# SheetMCU.net
KiCad netlist of a schematic drawn in Altium Designer
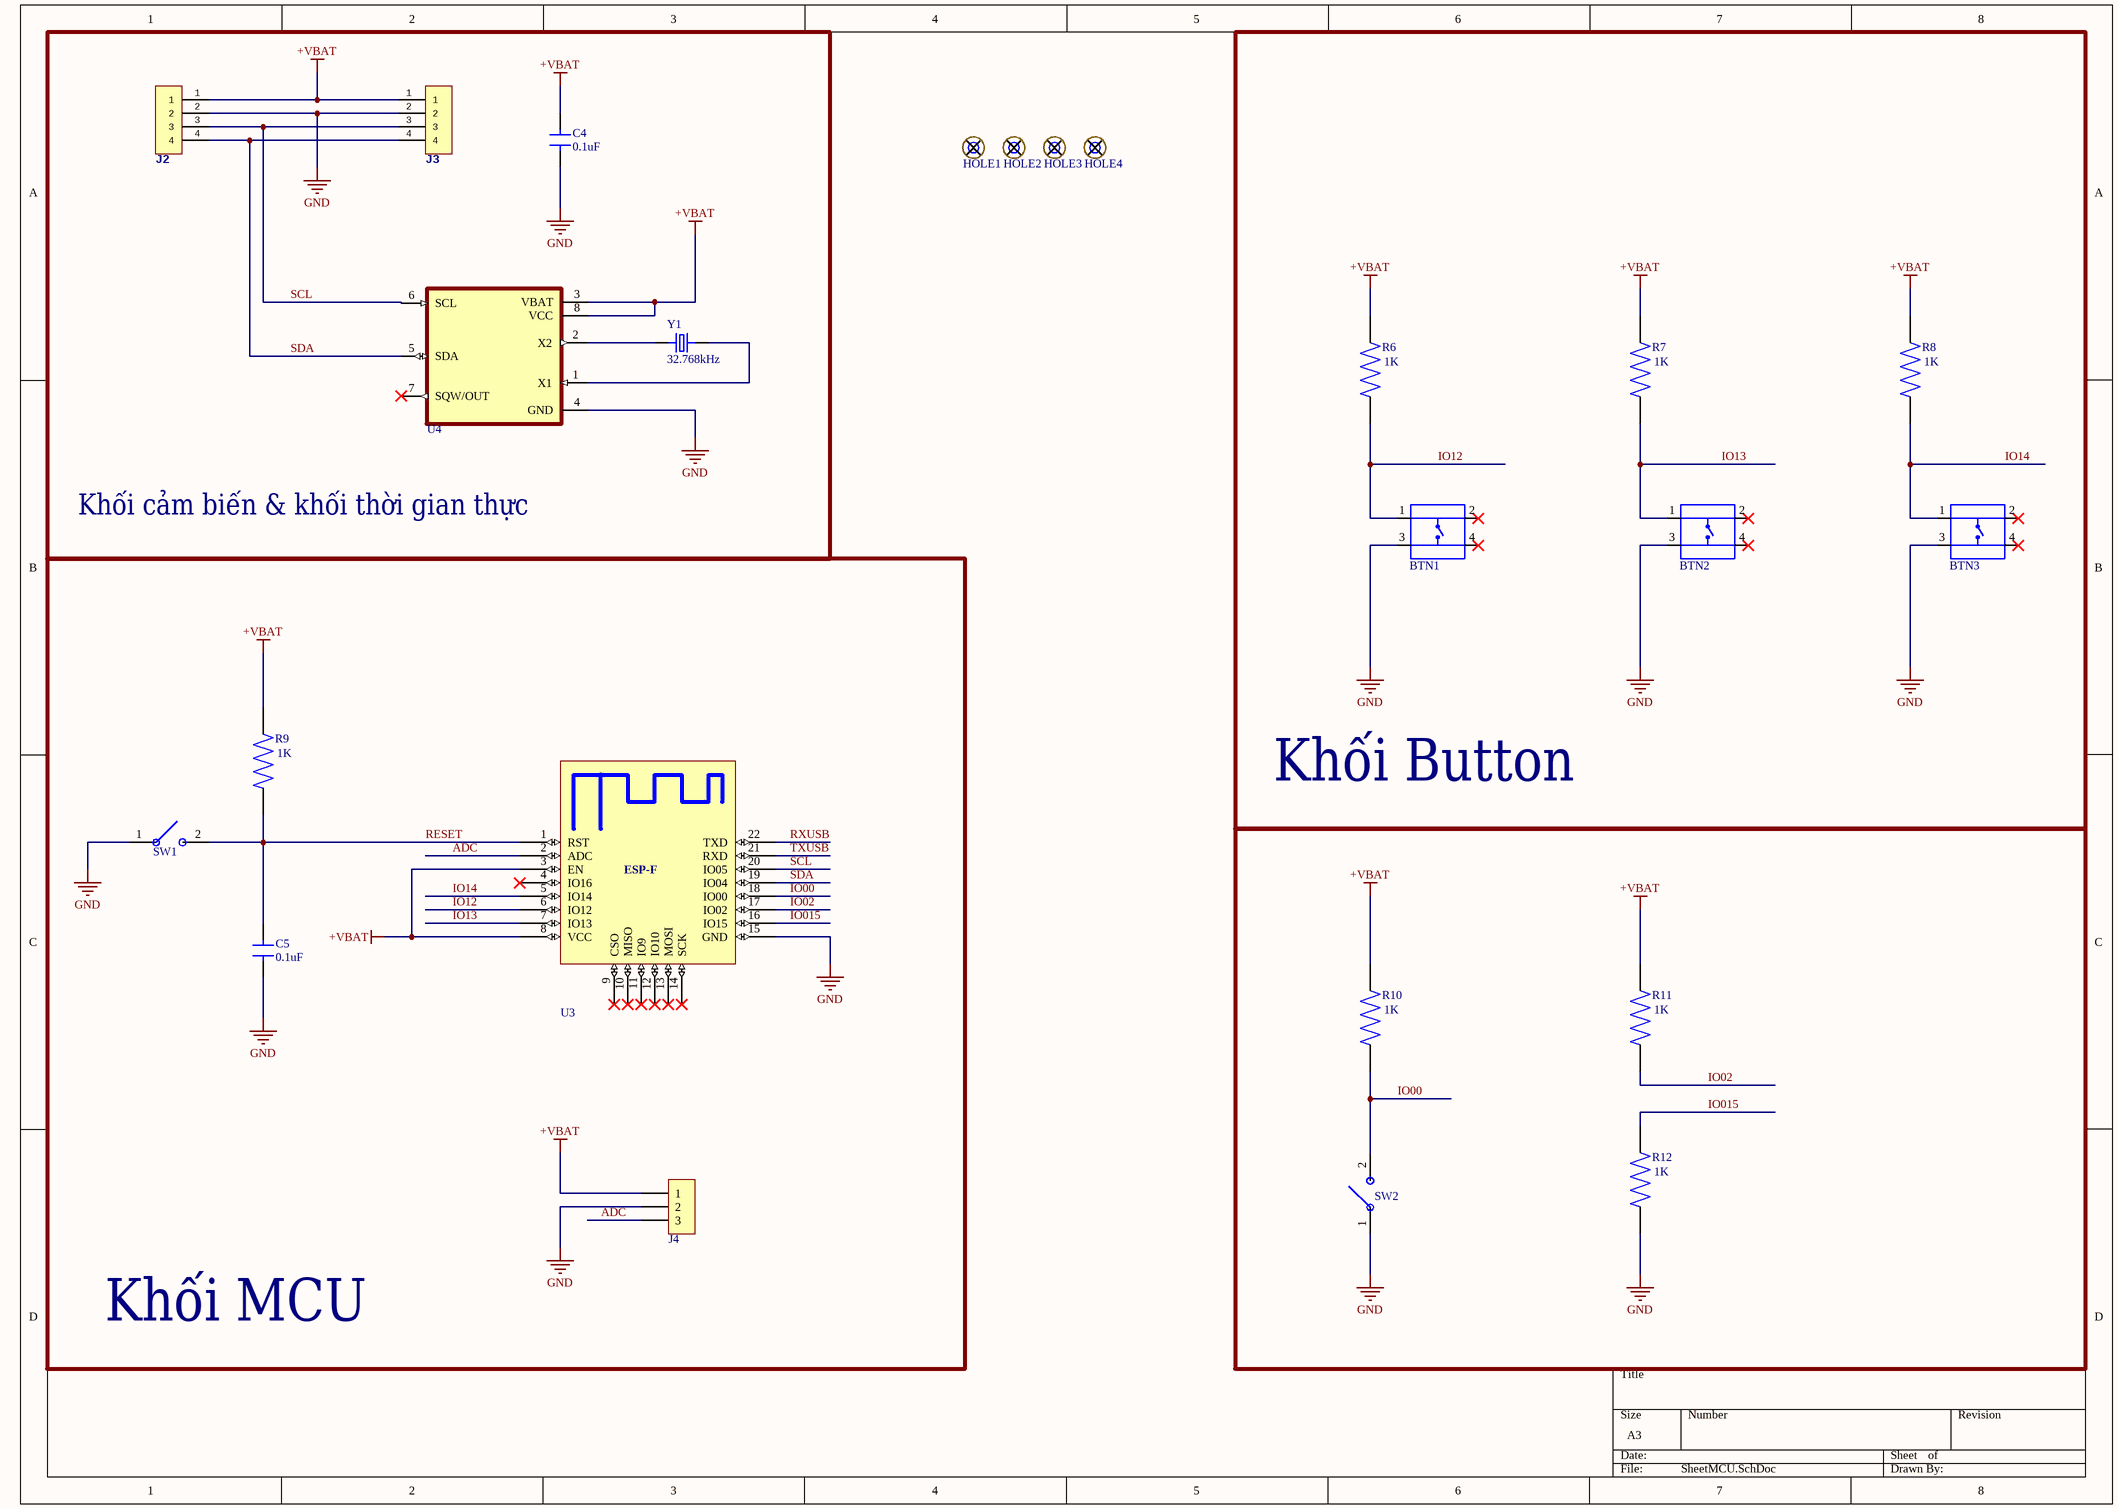
[diagram p0: SheetMCU.SchDoc]

(export (version "E")
  (design (tool "Eeschema 10.0.6"))
  (components
    (comp (ref "BTN1")
      (value "button 4x4")
      (footprint "SW_2-1825910-7")
      (description "Switch Tactile N.O. SPST Round Button PC Pins 0.05A 50VDC 1.57N Thru-Hole")
      (fields
        (field (name "MANUFACTURER") "E-Switch")
        (field (name "MANUFACTURER PART NUMBER") "TL1105BF160Q")
      )
      (libsource (lib "SchlibWatch") (part "TL1105BF160Q"))
    )
    (comp (ref "BTN2")
      (value "button 4x4")
      (footprint "SW_2-1825910-7")
      (description "Switch Tactile N.O. SPST Round Button PC Pins 0.05A 50VDC 1.57N Thru-Hole")
      (fields
        (field (name "MANUFACTURER") "E-Switch")
        (field (name "MANUFACTURER PART NUMBER") "TL1105BF160Q")
      )
      (libsource (lib "SchlibWatch") (part "TL1105BF160Q"))
    )
    (comp (ref "BTN3")
      (value "button 4x4")
      (footprint "SW_2-1825910-7")
      (description "Switch Tactile N.O. SPST Round Button PC Pins 0.05A 50VDC 1.57N Thru-Hole")
      (fields
        (field (name "MANUFACTURER") "E-Switch")
        (field (name "MANUFACTURER PART NUMBER") "TL1105BF160Q")
      )
      (libsource (lib "SchlibWatch") (part "TL1105BF160Q"))
    )
    (comp (ref "C4")
      (value "0.1uF")
      (footprint "CAP104 0.1UF 50V")
      (description "Cap Ceramic 0.1uF 50V X7R 10% SMD 2.0 x 1.2 mm 125 C Paper T/R")
      (fields
        (field (name "MANUFACTURER") "KEMET")
        (field (name "MANUFACTURER PART NUMBER") "C0805C104K5RACTU")
      )
      (libsource (lib "SchlibWatch") (part "C0805C104K5RACTU"))
    )
    (comp (ref "C5")
      (value "0.1uF")
      (footprint "CAP104 0.1UF 50V")
      (description "Cap Ceramic 0.1uF 50V X7R 10% SMD 2.0 x 1.2 mm 125 C Paper T/R")
      (fields
        (field (name "MANUFACTURER") "KEMET")
        (field (name "MANUFACTURER PART NUMBER") "C0805C104K5RACTU")
      )
      (libsource (lib "SchlibWatch") (part "C0805C104K5RACTU"))
    )
    (comp (ref "HOLE1")
      (value "Hole")
      (footprint "Hole 2MM")
      (description "Hole 3mm")
      (libsource (lib "SchlibWatch") (part "Hole 2mm"))
    )
    (comp (ref "HOLE2")
      (value "Hole")
      (footprint "Hole 2MM")
      (description "Hole 3mm")
      (libsource (lib "SchlibWatch") (part "Hole 2mm"))
    )
    (comp (ref "HOLE3")
      (value "Hole")
      (footprint "Hole 2MM")
      (description "Hole 3mm")
      (libsource (lib "SchlibWatch") (part "Hole 2mm"))
    )
    (comp (ref "HOLE4")
      (value "Hole")
      (footprint "Hole 2MM")
      (description "Hole 3mm")
      (libsource (lib "SchlibWatch") (part "Hole 2mm"))
    )
    (comp (ref "J2")
      (value "SAMTEC-HTSW-104-07-X-SJ")
      (footprint "Conn 4 Pos")
      (description "CONN HEADER 4 POS 2.54mm")
      (libsource (lib "SchlibWatch") (part "SAMTEC-HTSW-104-07-X-SJ"))
    )
    (comp (ref "J3")
      (value "SAMTEC-HTSW-104-07-X-SJ")
      (footprint "Conn 4 Pos")
      (description "CONN HEADER 4 POS 2.54mm")
      (libsource (lib "") (part "SAMTEC-HTSW-104-07-X-SJ_1"))
    )
    (comp (ref "J4")
      (value "CONN HEADER VERT 3POS 2.54MM")
      (footprint "CONN HEADER VERT 3POS 2.54MM")
      (description "Conn Unshrouded Header HDR 3 POS 2.54mm Solder ST Thru-Hole")
      (fields
        (field (name "MANUFACTURER") "TE Connectivity")
        (field (name "MANUFACTURER PART NUMBER") "87220-3")
      )
      (libsource (lib "SchlibWatch") (part "87220-3"))
    )
    (comp (ref "R6")
      (value "1K")
      (footprint "RC0805 1K OHM")
      (description "贴片电阻 1000Ω ± 1.00% 0.125W ± 100ppm/℃ 0805")
      (fields
        (field (name "MANUFACTURER") "Yageo")
        (field (name "MANUFACTURER PART NUMBER") "RC0805FR-071KL")
      )
      (libsource (lib "SchlibWatch") (part "RC0805FR-071KL"))
    )
    (comp (ref "R7")
      (value "1K")
      (footprint "RC0805 1K OHM")
      (description "贴片电阻 1000Ω ± 1.00% 0.125W ± 100ppm/℃ 0805")
      (fields
        (field (name "MANUFACTURER") "Yageo")
        (field (name "MANUFACTURER PART NUMBER") "RC0805FR-071KL")
      )
      (libsource (lib "SchlibWatch") (part "RC0805FR-071KL"))
    )
    (comp (ref "R8")
      (value "1K")
      (footprint "RC0805 1K OHM")
      (description "贴片电阻 1000Ω ± 1.00% 0.125W ± 100ppm/℃ 0805")
      (fields
        (field (name "MANUFACTURER") "Yageo")
        (field (name "MANUFACTURER PART NUMBER") "RC0805FR-071KL")
      )
      (libsource (lib "SchlibWatch") (part "RC0805FR-071KL"))
    )
    (comp (ref "R9")
      (value "1K")
      (footprint "RC0805 1K OHM")
      (description "贴片电阻 1000Ω ± 1.00% 0.125W ± 100ppm/℃ 0805")
      (fields
        (field (name "MANUFACTURER") "Yageo")
        (field (name "MANUFACTURER PART NUMBER") "RC0805FR-071KL")
      )
      (libsource (lib "SchlibWatch") (part "RC0805FR-071KL"))
    )
    (comp (ref "R10")
      (value "1K")
      (footprint "RC0805 1K OHM")
      (description "贴片电阻 1000Ω ± 1.00% 0.125W ± 100ppm/℃ 0805")
      (fields
        (field (name "MANUFACTURER") "Yageo")
        (field (name "MANUFACTURER PART NUMBER") "RC0805FR-071KL")
      )
      (libsource (lib "SchlibWatch") (part "RC0805FR-071KL"))
    )
    (comp (ref "R11")
      (value "1K")
      (footprint "RC0805 1K OHM")
      (description "贴片电阻 1000Ω ± 1.00% 0.125W ± 100ppm/℃ 0805")
      (fields
        (field (name "MANUFACTURER") "Yageo")
        (field (name "MANUFACTURER PART NUMBER") "RC0805FR-071KL")
      )
      (libsource (lib "SchlibWatch") (part "RC0805FR-071KL"))
    )
    (comp (ref "R12")
      (value "1K")
      (footprint "RC0805 1K OHM")
      (description "贴片电阻 1000Ω ± 1.00% 0.125W ± 100ppm/℃ 0805")
      (fields
        (field (name "MANUFACTURER") "Yageo")
        (field (name "MANUFACTURER PART NUMBER") "RC0805FR-071KL")
      )
      (libsource (lib "SchlibWatch") (part "RC0805FR-071KL"))
    )
    (comp (ref "SW1")
      (value "Switch")
      (footprint "PTS636 SM43J SMTR LFS")
      (description "Switch Reset")
      (fields
        (field (name "MANUFACTURER") "ITT C&K")
        (field (name "MANUFACTURER PART NUMBER") "PTS636SM43JSMTRLFS")
      )
      (libsource (lib "SchlibWatch") (part "PTS636SM43JSMTRLFS"))
    )
    (comp (ref "SW2")
      (value "Switch")
      (footprint "PTS636 SM43J SMTR LFS")
      (description "Switch Reset")
      (fields
        (field (name "MANUFACTURER") "ITT C&K")
        (field (name "MANUFACTURER PART NUMBER") "PTS636SM43JSMTRLFS")
      )
      (libsource (lib "SchlibWatch") (part "PTS636SM43JSMTRLFS"))
    )
    (comp (ref "U3")
      (value "ESP8266 ESP_F")
      (footprint "ESP8266 ESP-F")
      (description "ESP8266 SMT MODULE")
      (fields
        (field (name "MANUFACTURER") "Adafruit Industries")
        (field (name "MANUFACTURER PART NUMBER") "2491")
      )
      (libsource (lib "SchlibWatch") (part "2491"))
    )
    (comp (ref "U4")
      (value "DS1307Z+")
      (footprint "SOIC127P600X175-8N")
      (description "Real Time Clock _RTC_ IC Clock/Calendar 56B IÂ²C, 2-Wire Serial 8-SOIC _0.154, 3.90mm Width_")
      (fields (field (name "MF") "Maxim Integrated") (field (name "MP") "DS1307Z"))
      (libsource (lib "SchlibWatch") (part "DS1307Z+"))
    )
    (comp (ref "Y1")
      (value "32.768kHz")
      (footprint "XTAL_ECS-3X8X")
      (description "32.768kHz Â±20ppm Crystal 12.5pF 35 kOhms Cylindrical Can, Radial")
      (fields (field (name "MF") "ECS Inc.") (field (name "MP") "ECS-3X8X"))
      (libsource (lib "SchlibWatch") (part "ECS-3X8X"))
    )
  )
  (nets
    (net (code "1") (name "+VBAT") (class "Default")
      (node (ref "C4") (pin "2") (pinfunction "2_2") (pintype "passive"))
      (node (ref "J2") (pin "1") (pinfunction "1_1") (pintype "passive"))
      (node (ref "J3") (pin "1") (pinfunction "1_1") (pintype "passive"))
      (node (ref "J4") (pin "1") (pinfunction "1_1") (pintype "passive"))
      (node (ref "R10") (pin "2") (pinfunction "2_2") (pintype "passive"))
      (node (ref "R11") (pin "2") (pinfunction "2_2") (pintype "passive"))
      (node (ref "R6") (pin "2") (pinfunction "2_2") (pintype "passive"))
      (node (ref "R7") (pin "2") (pinfunction "2_2") (pintype "passive"))
      (node (ref "R8") (pin "2") (pinfunction "2_2") (pintype "passive"))
      (node (ref "R9") (pin "2") (pinfunction "2_2") (pintype "passive"))
      (node (ref "U3") (pin "3") (pinfunction "EN_3") (pintype "bidirectional"))
      (node (ref "U3") (pin "8") (pinfunction "VCC_8") (pintype "bidirectional"))
      (node (ref "U4") (pin "3") (pinfunction "VBAT_3") (pintype "power_in"))
      (node (ref "U4") (pin "8") (pinfunction "VCC_8") (pintype "power_in"))
    )
    (net (code "2") (name "/ADC") (class "Default")
      (node (ref "J4") (pin "3") (pinfunction "3_3") (pintype "passive"))
      (node (ref "U3") (pin "2") (pinfunction "ADC_2") (pintype "bidirectional"))
    )
    (net (code "3") (name "/IO00") (class "Default")
      (node (ref "R10") (pin "1") (pinfunction "1_1") (pintype "passive"))
      (node (ref "SW2") (pin "2") (pinfunction "2_2") (pintype "passive"))
      (node (ref "U3") (pin "18") (pinfunction "IO00_18") (pintype "bidirectional"))
    )
    (net (code "4") (name "/IO02") (class "Default")
      (node (ref "R11") (pin "1") (pinfunction "1_1") (pintype "passive"))
      (node (ref "U3") (pin "17") (pinfunction "IO02_17") (pintype "bidirectional"))
    )
    (net (code "5") (name "/IO12") (class "Default")
      (node (ref "BTN1") (pin "1") (pinfunction "1_1") (pintype "passive"))
      (node (ref "R6") (pin "1") (pinfunction "1_1") (pintype "passive"))
      (node (ref "U3") (pin "6") (pinfunction "IO12_6") (pintype "bidirectional"))
    )
    (net (code "6") (name "/IO13") (class "Default")
      (node (ref "BTN2") (pin "1") (pinfunction "1_1") (pintype "passive"))
      (node (ref "R7") (pin "1") (pinfunction "1_1") (pintype "passive"))
      (node (ref "U3") (pin "7") (pinfunction "IO13_7") (pintype "bidirectional"))
    )
    (net (code "7") (name "/IO14") (class "Default")
      (node (ref "BTN3") (pin "1") (pinfunction "1_1") (pintype "passive"))
      (node (ref "R8") (pin "1") (pinfunction "1_1") (pintype "passive"))
      (node (ref "U3") (pin "5") (pinfunction "IO14_5") (pintype "bidirectional"))
    )
    (net (code "8") (name "/IO015") (class "Default")
      (node (ref "R12") (pin "2") (pinfunction "2_2") (pintype "passive"))
      (node (ref "U3") (pin "16") (pinfunction "IO15_16") (pintype "bidirectional"))
    )
    (net (code "9") (name "/RESET") (class "Default")
      (node (ref "C5") (pin "2") (pinfunction "2_2") (pintype "passive"))
      (node (ref "R9") (pin "1") (pinfunction "1_1") (pintype "passive"))
      (node (ref "SW1") (pin "2") (pinfunction "2_2") (pintype "passive"))
      (node (ref "U3") (pin "1") (pinfunction "RST_1") (pintype "bidirectional"))
    )
    (net (code "10") (name "/RXUSB") (class "Default")
      (node (ref "U3") (pin "22") (pinfunction "TXD_22") (pintype "bidirectional"))
    )
    (net (code "11") (name "/SCL") (class "Default")
      (node (ref "J2") (pin "3") (pinfunction "3_3") (pintype "passive"))
      (node (ref "J3") (pin "3") (pinfunction "3_3") (pintype "passive"))
      (node (ref "U3") (pin "20") (pinfunction "IO05_20") (pintype "bidirectional"))
      (node (ref "U4") (pin "6") (pinfunction "SCL_6") (pintype "input"))
    )
    (net (code "12") (name "/SDA") (class "Default")
      (node (ref "J2") (pin "4") (pinfunction "4_4") (pintype "passive"))
      (node (ref "J3") (pin "4") (pinfunction "4_4") (pintype "passive"))
      (node (ref "U3") (pin "19") (pinfunction "IO04_19") (pintype "bidirectional"))
      (node (ref "U4") (pin "5") (pinfunction "SDA_5") (pintype "bidirectional"))
    )
    (net (code "13") (name "/TXUSB") (class "Default")
      (node (ref "U3") (pin "21") (pinfunction "RXD_21") (pintype "bidirectional"))
    )
    (net (code "14") (name "GND") (class "Default")
      (node (ref "BTN1") (pin "3") (pinfunction "3_3") (pintype "passive"))
      (node (ref "BTN2") (pin "3") (pinfunction "3_3") (pintype "passive"))
      (node (ref "BTN3") (pin "3") (pinfunction "3_3") (pintype "passive"))
      (node (ref "C4") (pin "1") (pinfunction "1_1") (pintype "passive"))
      (node (ref "C5") (pin "1") (pinfunction "1_1") (pintype "passive"))
      (node (ref "J2") (pin "2") (pinfunction "2_2") (pintype "passive"))
      (node (ref "J3") (pin "2") (pinfunction "2_2") (pintype "passive"))
      (node (ref "J4") (pin "2") (pinfunction "2_2") (pintype "passive"))
      (node (ref "R12") (pin "1") (pinfunction "1_1") (pintype "passive"))
      (node (ref "SW1") (pin "1") (pinfunction "1_1") (pintype "passive"))
      (node (ref "SW2") (pin "1") (pinfunction "1_1") (pintype "passive"))
      (node (ref "U3") (pin "15") (pinfunction "GND_15") (pintype "bidirectional"))
      (node (ref "U4") (pin "4") (pinfunction "GND_4") (pintype "power_in"))
    )
    (net (code "15") (name "Net-(U4-X1)") (class "Default")
      (node (ref "U4") (pin "1") (pinfunction "X1_1") (pintype "input"))
      (node (ref "Y1") (pin "2") (pinfunction "2_2") (pintype "passive"))
    )
    (net (code "16") (name "Net-(U4-X2)") (class "Default")
      (node (ref "U4") (pin "2") (pinfunction "X2_2") (pintype "output"))
      (node (ref "Y1") (pin "1") (pinfunction "1_1") (pintype "passive"))
    )
    (net (code "17") (name "unconnected-(BTN1-Pad2)") (class "Default")
      (node (ref "BTN1") (pin "2") (pinfunction "2_2") (pintype "passive+no_connect"))
    )
    (net (code "18") (name "unconnected-(BTN1-Pad4)") (class "Default")
      (node (ref "BTN1") (pin "4") (pinfunction "4_4") (pintype "passive+no_connect"))
    )
    (net (code "19") (name "unconnected-(BTN2-Pad2)") (class "Default")
      (node (ref "BTN2") (pin "2") (pinfunction "2_2") (pintype "passive+no_connect"))
    )
    (net (code "20") (name "unconnected-(BTN2-Pad4)") (class "Default")
      (node (ref "BTN2") (pin "4") (pinfunction "4_4") (pintype "passive+no_connect"))
    )
    (net (code "21") (name "unconnected-(BTN3-Pad2)") (class "Default")
      (node (ref "BTN3") (pin "2") (pinfunction "2_2") (pintype "passive+no_connect"))
    )
    (net (code "22") (name "unconnected-(BTN3-Pad4)") (class "Default")
      (node (ref "BTN3") (pin "4") (pinfunction "4_4") (pintype "passive+no_connect"))
    )
    (net (code "23") (name "unconnected-(U3-CSO-Pad9)") (class "Default")
      (node (ref "U3") (pin "9") (pinfunction "CSO_9") (pintype "bidirectional+no_connect"))
    )
    (net (code "24") (name "unconnected-(U3-IO9-Pad11)") (class "Default")
      (node (ref "U3") (pin "11") (pinfunction "IO9_11") (pintype "bidirectional+no_connect"))
    )
    (net (code "25") (name "unconnected-(U3-IO10-Pad12)") (class "Default")
      (node (ref "U3") (pin "12") (pinfunction "IO10_12") (pintype "bidirectional+no_connect"))
    )
    (net (code "26") (name "unconnected-(U3-IO16-Pad4)") (class "Default")
      (node (ref "U3") (pin "4") (pinfunction "IO16_4") (pintype "bidirectional+no_connect"))
    )
    (net (code "27") (name "unconnected-(U3-MISO-Pad10)") (class "Default")
      (node (ref "U3") (pin "10") (pinfunction "MISO_10") (pintype "bidirectional+no_connect"))
    )
    (net (code "28") (name "unconnected-(U3-MOSI-Pad13)") (class "Default")
      (node (ref "U3") (pin "13") (pinfunction "MOSI_13") (pintype "bidirectional+no_connect"))
    )
    (net (code "29") (name "unconnected-(U3-SCK-Pad14)") (class "Default")
      (node (ref "U3") (pin "14") (pinfunction "SCK_14") (pintype "bidirectional+no_connect"))
    )
    (net (code "30") (name "unconnected-(U4-SQW{slash}OUT-Pad7)") (class "Default")
      (node (ref "U4") (pin "7") (pinfunction "SQW/OUT_7") (pintype "output+no_connect"))
    )
  )
)
